# H_Bridge.net
KiCad netlist of a schematic drawn in EAGLE
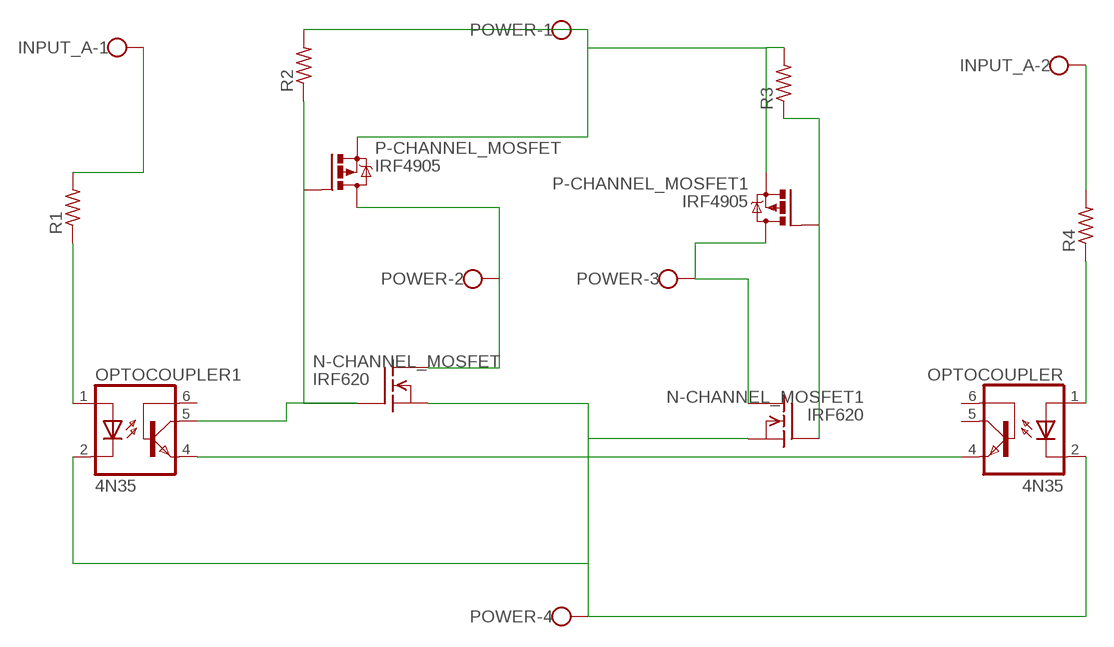
[diagram p0: schematic, sheet 1]

(export (version "E")
  (design (tool "Eeschema 10.0.6"))
  (components
    (comp (ref "INPUT_A")
      (value "W237-4")
      (footprint "eagle-import:W237-4")
      (libsource (lib "eagle-import") (part "W237-4"))
    )
    (comp (ref "N-CHANNEL_MOSFET")
      (value "IRF620")
      (footprint "eagle-import:TO220")
      (libsource (lib "eagle-import") (part "IRF620"))
    )
    (comp (ref "N-CHANNEL_MOSFET1")
      (value "IRF620")
      (footprint "eagle-import:TO220")
      (libsource (lib "eagle-import") (part "IRF620"))
    )
    (comp (ref "OPTOCOUPLER")
      (value "4N35")
      (footprint "eagle-import:DIL06")
      (fields (field (name "MF") "FAIRCHILD SEMICONDUCTOR"))
      (libsource (lib "eagle-import") (part "4N35"))
    )
    (comp (ref "OPTOCOUPLER1")
      (value "4N35")
      (footprint "eagle-import:DIL06")
      (fields (field (name "MF") "FAIRCHILD SEMICONDUCTOR"))
      (libsource (lib "eagle-import") (part "4N35"))
    )
    (comp (ref "P-CHANNEL_MOSFET")
      (value "IRF4905")
      (footprint "eagle-import:TO220BH")
      (libsource (lib "eagle-import") (part "IRF4905"))
    )
    (comp (ref "P-CHANNEL_MOSFET1")
      (value "IRF4905")
      (footprint "eagle-import:TO220BH")
      (libsource (lib "eagle-import") (part "IRF4905"))
    )
    (comp (ref "POWER")
      (value "W237-4")
      (footprint "eagle-import:W237-4")
      (libsource (lib "eagle-import") (part "W237-4"))
    )
    (comp (ref "R1")
      (value "R-US_0207/10")
      (footprint "eagle-import:0207_10")
      (libsource (lib "eagle-import") (part "R-US_0207/10"))
    )
    (comp (ref "R2")
      (value "R-US_0207/10")
      (footprint "eagle-import:0207_10")
      (libsource (lib "eagle-import") (part "R-US_0207/10"))
    )
    (comp (ref "R3")
      (value "R-US_0207/10")
      (footprint "eagle-import:0207_10")
      (libsource (lib "eagle-import") (part "R-US_0207/10"))
    )
    (comp (ref "R4")
      (value "R-US_0207/10")
      (footprint "eagle-import:0207_10")
      (libsource (lib "eagle-import") (part "R-US_0207/10"))
    )
  )
  (nets
    (net (code "1") (name "Net-(INPUT_AA-KL)") (class "Default")
      (node (ref "INPUT_A") (pin "1") (pinfunction "KL_1") (pintype "passive"))
      (node (ref "R1") (pin "2") (pinfunction "2_2") (pintype "passive"))
    )
    (net (code "2") (name "Net-(INPUT_AB-KL)") (class "Default")
      (node (ref "INPUT_A") (pin "2") (pinfunction "KL_2") (pintype "passive"))
      (node (ref "R4") (pin "2") (pinfunction "2_2") (pintype "passive"))
    )
    (net (code "3") (name "Net-(N-CHANNEL_MOSFET-D)") (class "Default")
      (node (ref "N-CHANNEL_MOSFET") (pin "2") (pinfunction "D_2") (pintype "passive"))
      (node (ref "P-CHANNEL_MOSFET") (pin "D") (pinfunction "D_D") (pintype "passive"))
      (node (ref "POWER") (pin "2") (pinfunction "KL_2") (pintype "passive"))
    )
    (net (code "4") (name "Net-(N-CHANNEL_MOSFET-G)") (class "Default")
      (node (ref "N-CHANNEL_MOSFET") (pin "1") (pinfunction "G_1") (pintype "passive"))
      (node (ref "OPTOCOUPLER1") (pin "5") (pinfunction "COL_5") (pintype "passive"))
      (node (ref "P-CHANNEL_MOSFET") (pin "G") (pinfunction "G_G") (pintype "passive"))
      (node (ref "R2") (pin "1") (pinfunction "1_1") (pintype "passive"))
    )
    (net (code "5") (name "Net-(N-CHANNEL_MOSFET-S)") (class "Default")
      (node (ref "N-CHANNEL_MOSFET") (pin "3") (pinfunction "S_3") (pintype "passive"))
      (node (ref "N-CHANNEL_MOSFET1") (pin "3") (pinfunction "S_3") (pintype "passive"))
      (node (ref "OPTOCOUPLER") (pin "2") (pinfunction "C_2") (pintype "passive"))
      (node (ref "OPTOCOUPLER") (pin "4") (pinfunction "EMI_4") (pintype "passive"))
      (node (ref "OPTOCOUPLER1") (pin "2") (pinfunction "C_2") (pintype "passive"))
      (node (ref "OPTOCOUPLER1") (pin "4") (pinfunction "EMI_4") (pintype "passive"))
      (node (ref "POWER") (pin "4") (pinfunction "KL_4") (pintype "passive"))
    )
    (net (code "6") (name "Net-(N-CHANNEL_MOSFET1-D)") (class "Default")
      (node (ref "N-CHANNEL_MOSFET1") (pin "2") (pinfunction "D_2") (pintype "passive"))
      (node (ref "P-CHANNEL_MOSFET1") (pin "D") (pinfunction "D_D") (pintype "passive"))
      (node (ref "POWER") (pin "3") (pinfunction "KL_3") (pintype "passive"))
    )
    (net (code "7") (name "Net-(N-CHANNEL_MOSFET1-G)") (class "Default")
      (node (ref "N-CHANNEL_MOSFET1") (pin "1") (pinfunction "G_1") (pintype "passive"))
      (node (ref "P-CHANNEL_MOSFET1") (pin "G") (pinfunction "G_G") (pintype "passive"))
      (node (ref "R3") (pin "1") (pinfunction "1_1") (pintype "passive"))
    )
    (net (code "8") (name "Net-(OPTOCOUPLER-A)") (class "Default")
      (node (ref "OPTOCOUPLER") (pin "1") (pinfunction "A_1") (pintype "passive"))
      (node (ref "R4") (pin "1") (pinfunction "1_1") (pintype "passive"))
    )
    (net (code "9") (name "Net-(OPTOCOUPLER1-A)") (class "Default")
      (node (ref "OPTOCOUPLER1") (pin "1") (pinfunction "A_1") (pintype "passive"))
      (node (ref "R1") (pin "1") (pinfunction "1_1") (pintype "passive"))
    )
    (net (code "10") (name "Net-(POWERA-KL)") (class "Default")
      (node (ref "P-CHANNEL_MOSFET") (pin "S") (pinfunction "S_S") (pintype "passive"))
      (node (ref "P-CHANNEL_MOSFET1") (pin "S") (pinfunction "S_S") (pintype "passive"))
      (node (ref "POWER") (pin "1") (pinfunction "KL_1") (pintype "passive"))
      (node (ref "R2") (pin "2") (pinfunction "2_2") (pintype "passive"))
      (node (ref "R3") (pin "2") (pinfunction "2_2") (pintype "passive"))
    )
    (net (code "11") (name "unconnected-(OPTOCOUPLER-BAS-Pad6)") (class "Default")
      (node (ref "OPTOCOUPLER") (pin "6") (pinfunction "BAS_6") (pintype "passive"))
    )
    (net (code "12") (name "unconnected-(OPTOCOUPLER-COL-Pad5)") (class "Default")
      (node (ref "OPTOCOUPLER") (pin "5") (pinfunction "COL_5") (pintype "passive"))
    )
    (net (code "13") (name "unconnected-(OPTOCOUPLER1-BAS-Pad6)") (class "Default")
      (node (ref "OPTOCOUPLER1") (pin "6") (pinfunction "BAS_6") (pintype "passive"))
    )
  )
)
